# PriusPP-esp12e.net
KiCad netlist of a schematic drawn in EAGLE
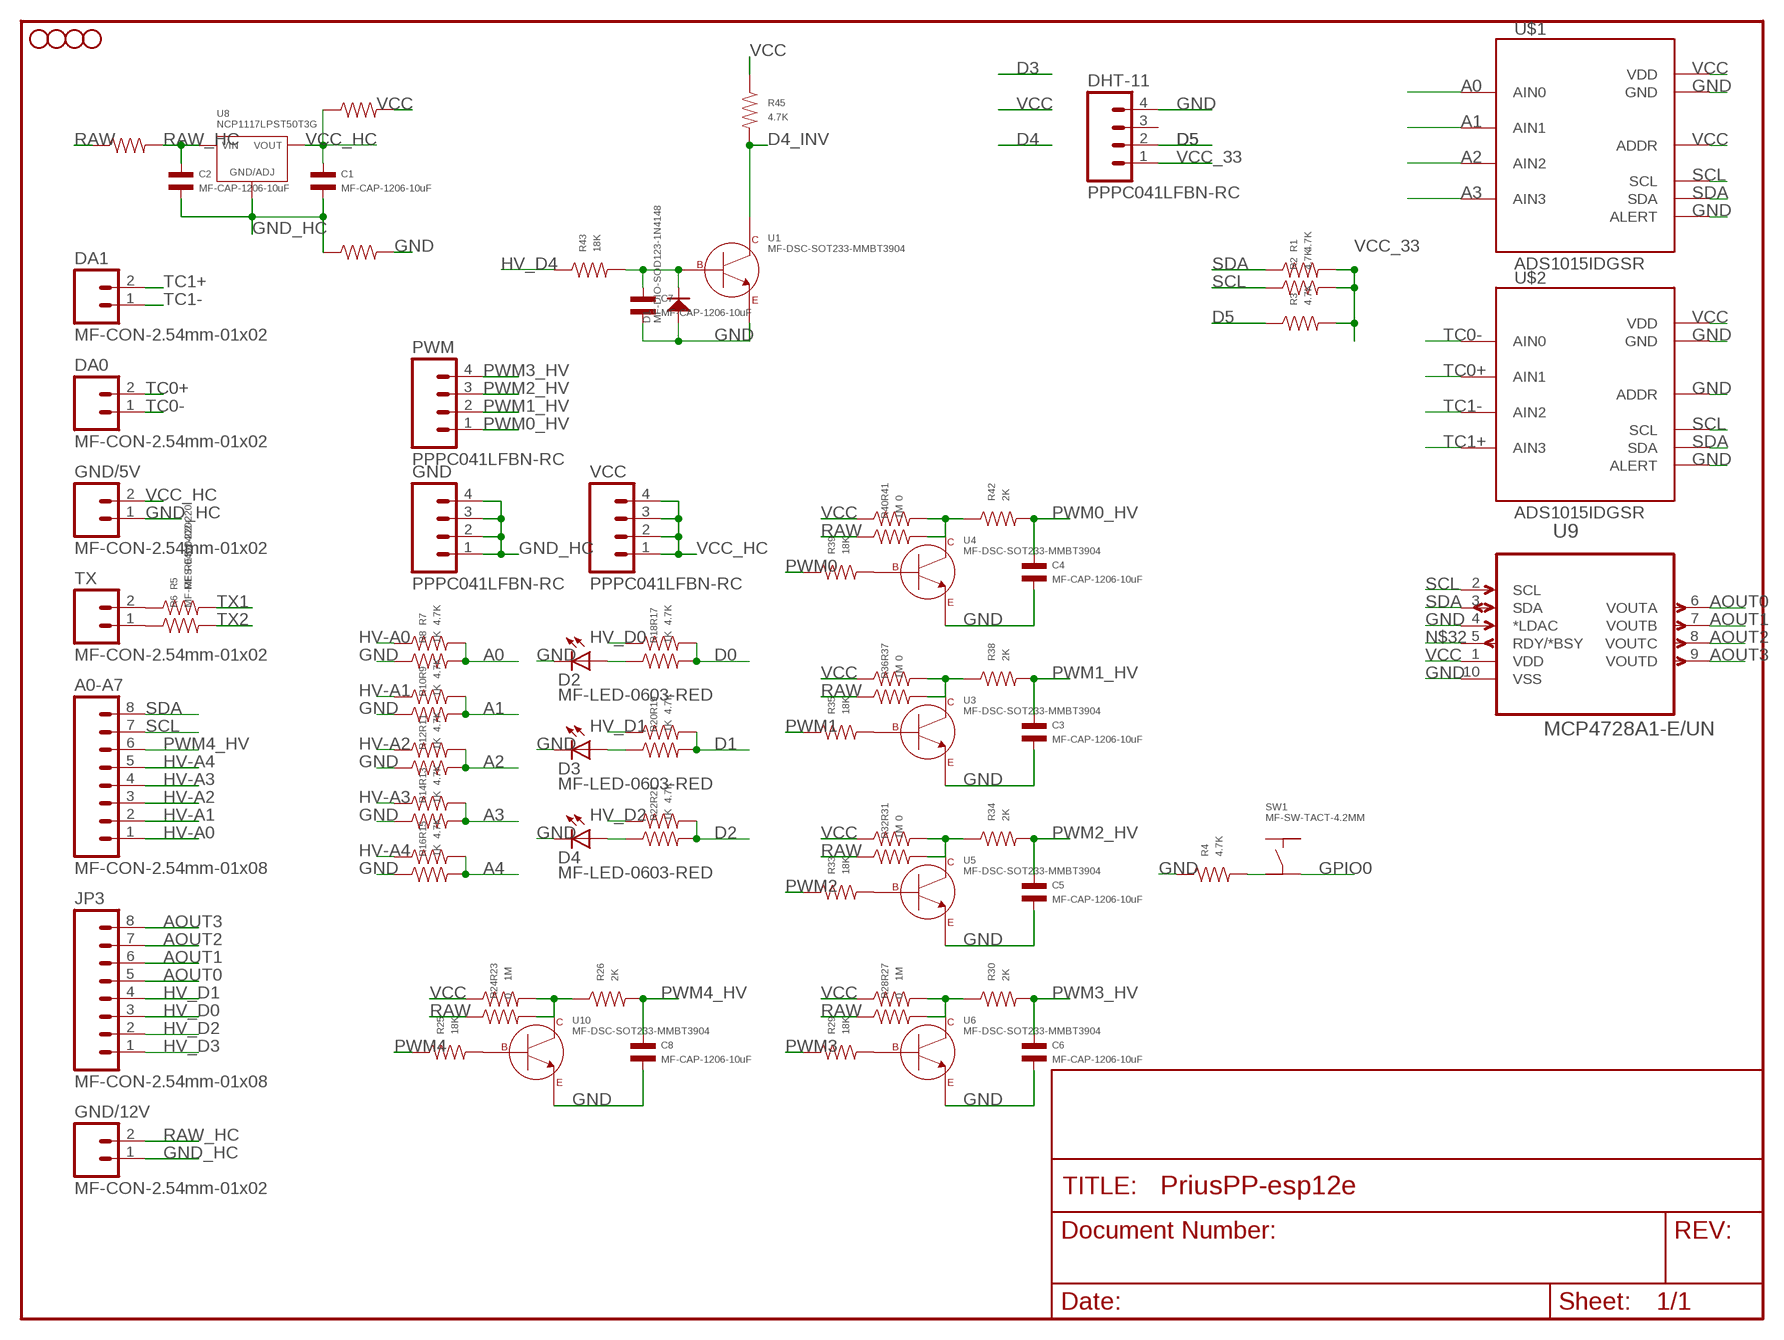
[diagram p0: schematic, sheet 1]

(export (version "E")
  (design (tool "Eeschema 10.0.6"))
  (components
    (comp (ref "A0-A7")
      (value "MF-CON-2.54mm-01x08")
      (footprint "eagle-import:1X08")
      (libsource (lib "eagle-import") (part "M081X08"))
    )
    (comp (ref "C1")
      (value "MF-CAP-1206-10uF")
      (footprint "eagle-import:C1206")
      (libsource (lib "eagle-import") (part "CAPACITOR_NP_1206"))
    )
    (comp (ref "C2")
      (value "MF-CAP-1206-10uF")
      (footprint "eagle-import:C1206")
      (libsource (lib "eagle-import") (part "CAPACITOR_NP_1206"))
    )
    (comp (ref "C3")
      (value "MF-CAP-1206-10uF")
      (footprint "eagle-import:C1206")
      (libsource (lib "eagle-import") (part "CAPACITOR_NP_1206"))
    )
    (comp (ref "C4")
      (value "MF-CAP-1206-10uF")
      (footprint "eagle-import:C1206")
      (libsource (lib "eagle-import") (part "CAPACITOR_NP_1206"))
    )
    (comp (ref "C5")
      (value "MF-CAP-1206-10uF")
      (footprint "eagle-import:C1206")
      (libsource (lib "eagle-import") (part "CAPACITOR_NP_1206"))
    )
    (comp (ref "C6")
      (value "MF-CAP-1206-10uF")
      (footprint "eagle-import:C1206")
      (libsource (lib "eagle-import") (part "CAPACITOR_NP_1206"))
    )
    (comp (ref "C7")
      (value "MF-CAP-1206-10uF")
      (footprint "eagle-import:C1206")
      (libsource (lib "eagle-import") (part "CAPACITOR_NP_1206"))
    )
    (comp (ref "C8")
      (value "MF-CAP-1206-10uF")
      (footprint "eagle-import:C1206")
      (libsource (lib "eagle-import") (part "CAPACITOR_NP_1206"))
    )
    (comp (ref "D1")
      (value "MF-DIO-SOD123-1N4148")
      (footprint "eagle-import:SOD-123")
      (fields (field (name "HOUSEPART") "YES"))
      (libsource (lib "eagle-import") (part "DIODES_SOD-123_1N4148"))
    )
    (comp (ref "D2")
      (value "MF-LED-0603-RED")
      (footprint "eagle-import:LED-0603")
      (libsource (lib "eagle-import") (part "LED-RED0603"))
    )
    (comp (ref "D3")
      (value "MF-LED-0603-RED")
      (footprint "eagle-import:LED-0603")
      (libsource (lib "eagle-import") (part "LED-RED0603"))
    )
    (comp (ref "D4")
      (value "MF-LED-0603-RED")
      (footprint "eagle-import:LED-0603")
      (libsource (lib "eagle-import") (part "LED-RED0603"))
    )
    (comp (ref "DA0")
      (value "MF-CON-2.54mm-01x02")
      (footprint "eagle-import:1X02")
      (libsource (lib "eagle-import") (part "M02PTH"))
    )
    (comp (ref "DA1")
      (value "MF-CON-2.54mm-01x02")
      (footprint "eagle-import:1X02")
      (libsource (lib "eagle-import") (part "M02PTH"))
    )
    (comp (ref "DHT-11")
      (value "PPPC041LFBN-RC")
      (footprint "eagle-import:1X04")
      (libsource (lib "eagle-import") (part "M04PTH"))
    )
    (comp (ref "GND")
      (value "PPPC041LFBN-RC")
      (footprint "eagle-import:1X04")
      (libsource (lib "eagle-import") (part "M04PTH"))
    )
    (comp (ref "GND/5V")
      (value "MF-CON-2.54mm-01x02")
      (footprint "eagle-import:1X02")
      (libsource (lib "eagle-import") (part "M02PTH"))
    )
    (comp (ref "GND/12V")
      (value "MF-CON-2.54mm-01x02")
      (footprint "eagle-import:1X02")
      (libsource (lib "eagle-import") (part "M02PTH"))
    )
    (comp (ref "JP3")
      (value "MF-CON-2.54mm-01x08")
      (footprint "eagle-import:1X08")
      (libsource (lib "eagle-import") (part "M081X08"))
    )
    (comp (ref "PWM")
      (value "PPPC041LFBN-RC")
      (footprint "eagle-import:1X04")
      (libsource (lib "eagle-import") (part "M04PTH"))
    )
    (comp (ref "R1")
      (value "4.7K")
      (footprint "eagle-import:R0402")
      (libsource (lib "eagle-import") (part "RESISTOR_0402"))
    )
    (comp (ref "R2")
      (value "4.7K")
      (footprint "eagle-import:R0402")
      (libsource (lib "eagle-import") (part "RESISTOR_0402"))
    )
    (comp (ref "R3")
      (value "4.7K")
      (footprint "eagle-import:R0402")
      (libsource (lib "eagle-import") (part "RESISTOR_0402"))
    )
    (comp (ref "R4")
      (value "4.7K")
      (footprint "eagle-import:R0402")
      (libsource (lib "eagle-import") (part "RESISTOR_0402"))
    )
    (comp (ref "R5")
      (value "MF-RES-0402-220")
      (footprint "eagle-import:R0402")
      (libsource (lib "eagle-import") (part "RESISTOR_0402"))
    )
    (comp (ref "R6")
      (value "MF-RES-0402-220")
      (footprint "eagle-import:R0402")
      (libsource (lib "eagle-import") (part "RESISTOR_0402"))
    )
    (comp (ref "R7")
      (value "4.7K")
      (footprint "eagle-import:R0402")
      (libsource (lib "eagle-import") (part "RESISTOR_0402"))
    )
    (comp (ref "R8")
      (value "1K")
      (footprint "eagle-import:R0402")
      (libsource (lib "eagle-import") (part "RESISTOR_0402"))
    )
    (comp (ref "R9")
      (value "4.7K")
      (footprint "eagle-import:R0402")
      (libsource (lib "eagle-import") (part "RESISTOR_0402"))
    )
    (comp (ref "R10")
      (value "1K")
      (footprint "eagle-import:R0402")
      (libsource (lib "eagle-import") (part "RESISTOR_0402"))
    )
    (comp (ref "R11")
      (value "4.7K")
      (footprint "eagle-import:R0402")
      (libsource (lib "eagle-import") (part "RESISTOR_0402"))
    )
    (comp (ref "R12")
      (value "1K")
      (footprint "eagle-import:R0402")
      (libsource (lib "eagle-import") (part "RESISTOR_0402"))
    )
    (comp (ref "R13")
      (value "4.7K")
      (footprint "eagle-import:R0402")
      (libsource (lib "eagle-import") (part "RESISTOR_0402"))
    )
    (comp (ref "R14")
      (value "1K")
      (footprint "eagle-import:R0402")
      (libsource (lib "eagle-import") (part "RESISTOR_0402"))
    )
    (comp (ref "R15")
      (value "4.7K")
      (footprint "eagle-import:R0402")
      (libsource (lib "eagle-import") (part "RESISTOR_0402"))
    )
    (comp (ref "R16")
      (value "1K")
      (footprint "eagle-import:R0402")
      (libsource (lib "eagle-import") (part "RESISTOR_0402"))
    )
    (comp (ref "R17")
      (value "4.7K")
      (footprint "eagle-import:R0402")
      (libsource (lib "eagle-import") (part "RESISTOR_0402"))
    )
    (comp (ref "R18")
      (value "1K")
      (footprint "eagle-import:R0402")
      (libsource (lib "eagle-import") (part "RESISTOR_0402"))
    )
    (comp (ref "R19")
      (value "4.7K")
      (footprint "eagle-import:R0402")
      (libsource (lib "eagle-import") (part "RESISTOR_0402"))
    )
    (comp (ref "R20")
      (value "1K")
      (footprint "eagle-import:R0402")
      (libsource (lib "eagle-import") (part "RESISTOR_0402"))
    )
    (comp (ref "R21")
      (value "4.7K")
      (footprint "eagle-import:R0402")
      (libsource (lib "eagle-import") (part "RESISTOR_0402"))
    )
    (comp (ref "R22")
      (value "1K")
      (footprint "eagle-import:R0402")
      (libsource (lib "eagle-import") (part "RESISTOR_0402"))
    )
    (comp (ref "R23")
      (value "1M")
      (footprint "eagle-import:R0402")
      (libsource (lib "eagle-import") (part "RESISTOR_0402"))
    )
    (comp (ref "R24")
      (value "0")
      (footprint "eagle-import:R0402")
      (libsource (lib "eagle-import") (part "RESISTOR_0402"))
    )
    (comp (ref "R25")
      (value "18K")
      (footprint "eagle-import:R0402")
      (libsource (lib "eagle-import") (part "RESISTOR_0402"))
    )
    (comp (ref "R26")
      (value "2K")
      (footprint "eagle-import:R0402")
      (libsource (lib "eagle-import") (part "RESISTOR_0402"))
    )
    (comp (ref "R27")
      (value "1M")
      (footprint "eagle-import:R0402")
      (libsource (lib "eagle-import") (part "RESISTOR_0402"))
    )
    (comp (ref "R28")
      (value "0")
      (footprint "eagle-import:R0402")
      (libsource (lib "eagle-import") (part "RESISTOR_0402"))
    )
    (comp (ref "R29")
      (value "18K")
      (footprint "eagle-import:R0402")
      (libsource (lib "eagle-import") (part "RESISTOR_0402"))
    )
    (comp (ref "R30")
      (value "2K")
      (footprint "eagle-import:R0402")
      (libsource (lib "eagle-import") (part "RESISTOR_0402"))
    )
    (comp (ref "R31")
      (value "0")
      (footprint "eagle-import:R0402")
      (libsource (lib "eagle-import") (part "RESISTOR_0402"))
    )
    (comp (ref "R32")
      (value "1M")
      (footprint "eagle-import:R0402")
      (libsource (lib "eagle-import") (part "RESISTOR_0402"))
    )
    (comp (ref "R33")
      (value "18K")
      (footprint "eagle-import:R0402")
      (libsource (lib "eagle-import") (part "RESISTOR_0402"))
    )
    (comp (ref "R34")
      (value "2K")
      (footprint "eagle-import:R0402")
      (libsource (lib "eagle-import") (part "RESISTOR_0402"))
    )
    (comp (ref "R35")
      (value "18K")
      (footprint "eagle-import:R0402")
      (libsource (lib "eagle-import") (part "RESISTOR_0402"))
    )
    (comp (ref "R36")
      (value "1M")
      (footprint "eagle-import:R0402")
      (libsource (lib "eagle-import") (part "RESISTOR_0402"))
    )
    (comp (ref "R37")
      (value "0")
      (footprint "eagle-import:R0402")
      (libsource (lib "eagle-import") (part "RESISTOR_0402"))
    )
    (comp (ref "R38")
      (value "2K")
      (footprint "eagle-import:R0402")
      (libsource (lib "eagle-import") (part "RESISTOR_0402"))
    )
    (comp (ref "R39")
      (value "18K")
      (footprint "eagle-import:R0402")
      (libsource (lib "eagle-import") (part "RESISTOR_0402"))
    )
    (comp (ref "R40")
      (value "1M")
      (footprint "eagle-import:R0402")
      (libsource (lib "eagle-import") (part "RESISTOR_0402"))
    )
    (comp (ref "R41")
      (value "0")
      (footprint "eagle-import:R0402")
      (libsource (lib "eagle-import") (part "RESISTOR_0402"))
    )
    (comp (ref "R42")
      (value "2K")
      (footprint "eagle-import:R0402")
      (libsource (lib "eagle-import") (part "RESISTOR_0402"))
    )
    (comp (ref "R43")
      (value "18K")
      (footprint "eagle-import:R0402")
      (libsource (lib "eagle-import") (part "RESISTOR_0402"))
    )
    (comp (ref "R45")
      (value "4.7K")
      (footprint "eagle-import:R0402")
      (libsource (lib "eagle-import") (part "RESISTOR_0402"))
    )
    (comp (ref "RIN7")
      (value "MF-RES-0603-0")
      (footprint "eagle-import:1206")
      (libsource (lib "eagle-import") (part "RESISTOR1206"))
    )
    (comp (ref "RIN8")
      (value "MF-RES-0603-0")
      (footprint "eagle-import:1206")
      (libsource (lib "eagle-import") (part "RESISTOR1206"))
    )
    (comp (ref "RIN19")
      (value "MF-RES-0603-0")
      (footprint "eagle-import:1206")
      (libsource (lib "eagle-import") (part "RESISTOR1206"))
    )
    (comp (ref "STANDOFF2")
      (value "STAND-OFF")
      (footprint "eagle-import:STAND-OFF")
      (libsource (lib "eagle-import") (part "STAND-OFF"))
    )
    (comp (ref "STANDOFF3")
      (value "STAND-OFF")
      (footprint "eagle-import:STAND-OFF")
      (libsource (lib "eagle-import") (part "STAND-OFF"))
    )
    (comp (ref "STANDOFF4")
      (value "STAND-OFF")
      (footprint "eagle-import:STAND-OFF")
      (libsource (lib "eagle-import") (part "STAND-OFF"))
    )
    (comp (ref "STANDOFF5")
      (value "STAND-OFF")
      (footprint "eagle-import:STAND-OFF")
      (libsource (lib "eagle-import") (part "STAND-OFF"))
    )
    (comp (ref "SW1")
      (value "MF-SW-TACT-4.2MM")
      (footprint "eagle-import:TACT4.2MM")
      (fields (field (name "HOUSEPART") "YES"))
      (libsource (lib "eagle-import") (part "TACT_4.2MM"))
    )
    (comp (ref "TX")
      (value "MF-CON-2.54mm-01x02")
      (footprint "eagle-import:1X02")
      (libsource (lib "eagle-import") (part "M02PTH"))
    )
    (comp (ref "U$1")
      (value "ADS1015IDGSR")
      (footprint "eagle-import:MSOP10_0.5")
      (libsource (lib "eagle-import") (part "ADS1015IDGT"))
    )
    (comp (ref "U$2")
      (value "ADS1015IDGSR")
      (footprint "eagle-import:MSOP10_0.5")
      (libsource (lib "eagle-import") (part "ADS1015IDGT"))
    )
    (comp (ref "U1")
      (value "MF-DSC-SOT233-MMBT3904")
      (footprint "eagle-import:SOT-23-3")
      (fields (field (name "HOUSEPART") "YES"))
      (libsource (lib "eagle-import") (part "NPN_BJT_SOT-23-3MMBT3904"))
    )
    (comp (ref "U3")
      (value "MF-DSC-SOT233-MMBT3904")
      (footprint "eagle-import:SOT-23-3")
      (fields (field (name "HOUSEPART") "YES"))
      (libsource (lib "eagle-import") (part "NPN_BJT_SOT-23-3MMBT3904"))
    )
    (comp (ref "U4")
      (value "MF-DSC-SOT233-MMBT3904")
      (footprint "eagle-import:SOT-23-3")
      (fields (field (name "HOUSEPART") "YES"))
      (libsource (lib "eagle-import") (part "NPN_BJT_SOT-23-3MMBT3904"))
    )
    (comp (ref "U5")
      (value "MF-DSC-SOT233-MMBT3904")
      (footprint "eagle-import:SOT-23-3")
      (fields (field (name "HOUSEPART") "YES"))
      (libsource (lib "eagle-import") (part "NPN_BJT_SOT-23-3MMBT3904"))
    )
    (comp (ref "U6")
      (value "MF-DSC-SOT233-MMBT3904")
      (footprint "eagle-import:SOT-23-3")
      (fields (field (name "HOUSEPART") "YES"))
      (libsource (lib "eagle-import") (part "NPN_BJT_SOT-23-3MMBT3904"))
    )
    (comp (ref "U8")
      (value "NCP1117LPST50T3G")
      (footprint "eagle-import:SOT-223-3")
      (fields (field (name "HOUSEPART") "NO"))
      (libsource (lib "eagle-import") (part "NCP1117LPST50T3G"))
    )
    (comp (ref "U9")
      (value "MCP4728A1-E/UN")
      (footprint "eagle-import:SOP50P490X110-10N")
      (fields (field (name "MPN") "MCP4728-E/UN"))
      (libsource (lib "eagle-import") (part "MCP4728-E/UN"))
    )
    (comp (ref "U10")
      (value "MF-DSC-SOT233-MMBT3904")
      (footprint "eagle-import:SOT-23-3")
      (fields (field (name "HOUSEPART") "YES"))
      (libsource (lib "eagle-import") (part "NPN_BJT_SOT-23-3MMBT3904"))
    )
    (comp (ref "VCC")
      (value "PPPC041LFBN-RC")
      (footprint "eagle-import:1X04")
      (libsource (lib "eagle-import") (part "M04PTH"))
    )
  )
  (nets
    (net (code "1") (name "/A0") (class "Default")
      (node (ref "R7") (pin "P$2") (pinfunction "P$2_P$2") (pintype "passive"))
      (node (ref "R8") (pin "P$2") (pinfunction "P$2_P$2") (pintype "passive"))
      (node (ref "U$1") (pin "4") (pinfunction "AIN0_4") (pintype "input"))
    )
    (net (code "2") (name "/A1") (class "Default")
      (node (ref "R10") (pin "P$2") (pinfunction "P$2_P$2") (pintype "passive"))
      (node (ref "R9") (pin "P$2") (pinfunction "P$2_P$2") (pintype "passive"))
      (node (ref "U$1") (pin "5") (pinfunction "AIN1_5") (pintype "input"))
    )
    (net (code "3") (name "/A2") (class "Default")
      (node (ref "R11") (pin "P$2") (pinfunction "P$2_P$2") (pintype "passive"))
      (node (ref "R12") (pin "P$2") (pinfunction "P$2_P$2") (pintype "passive"))
      (node (ref "U$1") (pin "6") (pinfunction "AIN2_6") (pintype "input"))
    )
    (net (code "4") (name "/A3") (class "Default")
      (node (ref "R13") (pin "P$2") (pinfunction "P$2_P$2") (pintype "passive"))
      (node (ref "R14") (pin "P$2") (pinfunction "P$2_P$2") (pintype "passive"))
      (node (ref "U$1") (pin "7") (pinfunction "AIN3_7") (pintype "input"))
    )
    (net (code "5") (name "/A4") (class "Default")
      (node (ref "R15") (pin "P$2") (pinfunction "P$2_P$2") (pintype "passive"))
      (node (ref "R16") (pin "P$2") (pinfunction "P$2_P$2") (pintype "passive"))
    )
    (net (code "6") (name "/AOUT0") (class "Default")
      (node (ref "JP3") (pin "5") (pinfunction "5_5") (pintype "passive"))
      (node (ref "U9") (pin "6") (pinfunction "VOUTA_6") (pintype "output"))
    )
    (net (code "7") (name "/AOUT1") (class "Default")
      (node (ref "JP3") (pin "6") (pinfunction "6_6") (pintype "passive"))
      (node (ref "U9") (pin "7") (pinfunction "VOUTB_7") (pintype "output"))
    )
    (net (code "8") (name "/AOUT2") (class "Default")
      (node (ref "JP3") (pin "7") (pinfunction "7_7") (pintype "passive"))
      (node (ref "U9") (pin "8") (pinfunction "VOUTC_8") (pintype "output"))
    )
    (net (code "9") (name "/AOUT3") (class "Default")
      (node (ref "JP3") (pin "8") (pinfunction "8_8") (pintype "passive"))
      (node (ref "U9") (pin "9") (pinfunction "VOUTD_9") (pintype "output"))
    )
    (net (code "10") (name "/D0") (class "Default")
      (node (ref "R17") (pin "P$2") (pinfunction "P$2_P$2") (pintype "passive"))
      (node (ref "R18") (pin "P$2") (pinfunction "P$2_P$2") (pintype "passive"))
    )
    (net (code "11") (name "/D1") (class "Default")
      (node (ref "R19") (pin "P$2") (pinfunction "P$2_P$2") (pintype "passive"))
      (node (ref "R20") (pin "P$2") (pinfunction "P$2_P$2") (pintype "passive"))
    )
    (net (code "12") (name "/D2") (class "Default")
      (node (ref "R21") (pin "P$2") (pinfunction "P$2_P$2") (pintype "passive"))
      (node (ref "R22") (pin "P$2") (pinfunction "P$2_P$2") (pintype "passive"))
    )
    (net (code "15") (name "/D4_INV") (class "Default")
      (node (ref "R45") (pin "P$2") (pinfunction "P$2_P$2") (pintype "passive"))
      (node (ref "U1") (pin "P$3") (pinfunction "COLLECTOR_P$3") (pintype "bidirectional"))
    )
    (net (code "16") (name "/D5") (class "Default")
      (node (ref "DHT-11") (pin "2") (pinfunction "2_2") (pintype "passive"))
      (node (ref "R3") (pin "P$1") (pinfunction "P$1_P$1") (pintype "passive"))
    )
    (net (code "17") (name "/GND") (class "Default")
      (node (ref "C3") (pin "P$2") (pinfunction "P$2_P$2") (pintype "passive"))
      (node (ref "C4") (pin "P$2") (pinfunction "P$2_P$2") (pintype "passive"))
      (node (ref "C5") (pin "P$2") (pinfunction "P$2_P$2") (pintype "passive"))
      (node (ref "C6") (pin "P$2") (pinfunction "P$2_P$2") (pintype "passive"))
      (node (ref "C7") (pin "P$2") (pinfunction "P$2_P$2") (pintype "passive"))
      (node (ref "C8") (pin "P$2") (pinfunction "P$2_P$2") (pintype "passive"))
      (node (ref "D1") (pin "ANODE") (pinfunction "ANODE_ANODE") (pintype "bidirectional"))
      (node (ref "D2") (pin "C") (pinfunction "C_C") (pintype "passive"))
      (node (ref "D3") (pin "C") (pinfunction "C_C") (pintype "passive"))
      (node (ref "D4") (pin "C") (pinfunction "C_C") (pintype "passive"))
      (node (ref "DHT-11") (pin "4") (pinfunction "4_4") (pintype "passive"))
      (node (ref "R10") (pin "P$1") (pinfunction "P$1_P$1") (pintype "passive"))
      (node (ref "R12") (pin "P$1") (pinfunction "P$1_P$1") (pintype "passive"))
      (node (ref "R14") (pin "P$1") (pinfunction "P$1_P$1") (pintype "passive"))
      (node (ref "R16") (pin "P$1") (pinfunction "P$1_P$1") (pintype "passive"))
      (node (ref "R4") (pin "P$1") (pinfunction "P$1_P$1") (pintype "passive"))
      (node (ref "R8") (pin "P$1") (pinfunction "P$1_P$1") (pintype "passive"))
      (node (ref "RIN8") (pin "2") (pinfunction "2_2") (pintype "passive"))
      (node (ref "U$1") (pin "2") (pinfunction "ALERT_2") (pintype "output"))
      (node (ref "U$1") (pin "3") (pinfunction "GND_3") (pintype "power_in"))
      (node (ref "U$2") (pin "1") (pinfunction "ADDR_1") (pintype "input"))
      (node (ref "U$2") (pin "2") (pinfunction "ALERT_2") (pintype "output"))
      (node (ref "U$2") (pin "3") (pinfunction "GND_3") (pintype "power_in"))
      (node (ref "U1") (pin "P$2") (pinfunction "EMITTER_P$2") (pintype "bidirectional"))
      (node (ref "U10") (pin "P$2") (pinfunction "EMITTER_P$2") (pintype "bidirectional"))
      (node (ref "U3") (pin "P$2") (pinfunction "EMITTER_P$2") (pintype "bidirectional"))
      (node (ref "U4") (pin "P$2") (pinfunction "EMITTER_P$2") (pintype "bidirectional"))
      (node (ref "U5") (pin "P$2") (pinfunction "EMITTER_P$2") (pintype "bidirectional"))
      (node (ref "U6") (pin "P$2") (pinfunction "EMITTER_P$2") (pintype "bidirectional"))
      (node (ref "U9") (pin "10") (pinfunction "VSS_10") (pintype "power_in"))
      (node (ref "U9") (pin "4") (pinfunction "*LDAC_4") (pintype "input"))
    )
    (net (code "18") (name "/GND_HC") (class "Default")
      (node (ref "C1") (pin "P$2") (pinfunction "P$2_P$2") (pintype "passive"))
      (node (ref "C2") (pin "P$2") (pinfunction "P$2_P$2") (pintype "passive"))
      (node (ref "GND") (pin "1") (pinfunction "1_1") (pintype "passive"))
      (node (ref "GND") (pin "2") (pinfunction "2_2") (pintype "passive"))
      (node (ref "GND") (pin "3") (pinfunction "3_3") (pintype "passive"))
      (node (ref "GND") (pin "4") (pinfunction "4_4") (pintype "passive"))
      (node (ref "GND/12V") (pin "1") (pinfunction "1_1") (pintype "passive"))
      (node (ref "GND/5V") (pin "1") (pinfunction "1_1") (pintype "passive"))
      (node (ref "RIN8") (pin "1") (pinfunction "1_1") (pintype "passive"))
      (node (ref "U8") (pin "P$2") (pinfunction "GND/ADJ_P$2") (pintype "bidirectional"))
    )
    (net (code "19") (name "/GPIO0") (class "Default")
      (node (ref "SW1") (pin "P$4") (pinfunction "P$4_P$4") (pintype "bidirectional"))
    )
    (net (code "20") (name "/HV-A0") (class "Default")
      (node (ref "A0-A7") (pin "1") (pinfunction "1_1") (pintype "passive"))
      (node (ref "R7") (pin "P$1") (pinfunction "P$1_P$1") (pintype "passive"))
    )
    (net (code "21") (name "/HV-A1") (class "Default")
      (node (ref "A0-A7") (pin "2") (pinfunction "2_2") (pintype "passive"))
      (node (ref "R9") (pin "P$1") (pinfunction "P$1_P$1") (pintype "passive"))
    )
    (net (code "22") (name "/HV-A2") (class "Default")
      (node (ref "A0-A7") (pin "3") (pinfunction "3_3") (pintype "passive"))
      (node (ref "R11") (pin "P$1") (pinfunction "P$1_P$1") (pintype "passive"))
    )
    (net (code "23") (name "/HV-A3") (class "Default")
      (node (ref "A0-A7") (pin "4") (pinfunction "4_4") (pintype "passive"))
      (node (ref "R13") (pin "P$1") (pinfunction "P$1_P$1") (pintype "passive"))
    )
    (net (code "24") (name "/HV-A4") (class "Default")
      (node (ref "A0-A7") (pin "5") (pinfunction "5_5") (pintype "passive"))
      (node (ref "R15") (pin "P$1") (pinfunction "P$1_P$1") (pintype "passive"))
    )
    (net (code "25") (name "/HV_D0") (class "Default")
      (node (ref "JP3") (pin "3") (pinfunction "3_3") (pintype "passive"))
      (node (ref "R17") (pin "P$1") (pinfunction "P$1_P$1") (pintype "passive"))
    )
    (net (code "26") (name "/HV_D1") (class "Default")
      (node (ref "JP3") (pin "4") (pinfunction "4_4") (pintype "passive"))
      (node (ref "R19") (pin "P$1") (pinfunction "P$1_P$1") (pintype "passive"))
    )
    (net (code "27") (name "/HV_D2") (class "Default")
      (node (ref "JP3") (pin "2") (pinfunction "2_2") (pintype "passive"))
      (node (ref "R21") (pin "P$1") (pinfunction "P$1_P$1") (pintype "passive"))
    )
    (net (code "28") (name "/HV_D3") (class "Default")
      (node (ref "JP3") (pin "1") (pinfunction "1_1") (pintype "passive"))
    )
    (net (code "29") (name "/HV_D4") (class "Default")
      (node (ref "R43") (pin "P$1") (pinfunction "P$1_P$1") (pintype "passive"))
    )
    (net (code "30") (name "/N$32") (class "Default")
      (node (ref "U9") (pin "5") (pinfunction "RDY/*BSY_5") (pintype "output"))
    )
    (net (code "31") (name "/PWM0") (class "Default")
      (node (ref "R39") (pin "P$1") (pinfunction "P$1_P$1") (pintype "passive"))
    )
    (net (code "32") (name "/PWM0_HV") (class "Default")
      (node (ref "C4") (pin "P$1") (pinfunction "P$1_P$1") (pintype "passive"))
      (node (ref "PWM") (pin "1") (pinfunction "1_1") (pintype "passive"))
      (node (ref "R42") (pin "P$2") (pinfunction "P$2_P$2") (pintype "passive"))
    )
    (net (code "33") (name "/PWM1") (class "Default")
      (node (ref "R35") (pin "P$1") (pinfunction "P$1_P$1") (pintype "passive"))
    )
    (net (code "34") (name "/PWM1_HV") (class "Default")
      (node (ref "C3") (pin "P$1") (pinfunction "P$1_P$1") (pintype "passive"))
      (node (ref "PWM") (pin "2") (pinfunction "2_2") (pintype "passive"))
      (node (ref "R38") (pin "P$2") (pinfunction "P$2_P$2") (pintype "passive"))
    )
    (net (code "35") (name "/PWM2") (class "Default")
      (node (ref "R33") (pin "P$1") (pinfunction "P$1_P$1") (pintype "passive"))
    )
    (net (code "36") (name "/PWM2_HV") (class "Default")
      (node (ref "C5") (pin "P$1") (pinfunction "P$1_P$1") (pintype "passive"))
      (node (ref "PWM") (pin "3") (pinfunction "3_3") (pintype "passive"))
      (node (ref "R34") (pin "P$2") (pinfunction "P$2_P$2") (pintype "passive"))
    )
    (net (code "37") (name "/PWM3") (class "Default")
      (node (ref "R29") (pin "P$1") (pinfunction "P$1_P$1") (pintype "passive"))
    )
    (net (code "38") (name "/PWM3_HV") (class "Default")
      (node (ref "C6") (pin "P$1") (pinfunction "P$1_P$1") (pintype "passive"))
      (node (ref "PWM") (pin "4") (pinfunction "4_4") (pintype "passive"))
      (node (ref "R30") (pin "P$2") (pinfunction "P$2_P$2") (pintype "passive"))
    )
    (net (code "39") (name "/PWM4") (class "Default")
      (node (ref "R25") (pin "P$1") (pinfunction "P$1_P$1") (pintype "passive"))
    )
    (net (code "40") (name "/PWM4_HV") (class "Default")
      (node (ref "A0-A7") (pin "6") (pinfunction "6_6") (pintype "passive"))
      (node (ref "C8") (pin "P$1") (pinfunction "P$1_P$1") (pintype "passive"))
      (node (ref "R26") (pin "P$2") (pinfunction "P$2_P$2") (pintype "passive"))
    )
    (net (code "41") (name "/RAW") (class "Default")
      (node (ref "R24") (pin "P$1") (pinfunction "P$1_P$1") (pintype "passive"))
      (node (ref "R28") (pin "P$1") (pinfunction "P$1_P$1") (pintype "passive"))
      (node (ref "R32") (pin "P$1") (pinfunction "P$1_P$1") (pintype "passive"))
      (node (ref "R36") (pin "P$1") (pinfunction "P$1_P$1") (pintype "passive"))
      (node (ref "R40") (pin "P$1") (pinfunction "P$1_P$1") (pintype "passive"))
      (node (ref "RIN19") (pin "1") (pinfunction "1_1") (pintype "passive"))
    )
    (net (code "42") (name "/RAW_HC") (class "Default")
      (node (ref "C2") (pin "P$1") (pinfunction "P$1_P$1") (pintype "passive"))
      (node (ref "GND/12V") (pin "2") (pinfunction "2_2") (pintype "passive"))
      (node (ref "RIN19") (pin "2") (pinfunction "2_2") (pintype "passive"))
      (node (ref "U8") (pin "P$4") (pinfunction "VIN_P$4") (pintype "bidirectional"))
    )
    (net (code "43") (name "/SCL") (class "Default")
      (node (ref "A0-A7") (pin "7") (pinfunction "7_7") (pintype "passive"))
      (node (ref "R2") (pin "P$1") (pinfunction "P$1_P$1") (pintype "passive"))
      (node (ref "U$1") (pin "10") (pinfunction "SCL_10") (pintype "bidirectional"))
      (node (ref "U$2") (pin "10") (pinfunction "SCL_10") (pintype "bidirectional"))
      (node (ref "U9") (pin "2") (pinfunction "SCL_2") (pintype "input"))
    )
    (net (code "44") (name "/SDA") (class "Default")
      (node (ref "A0-A7") (pin "8") (pinfunction "8_8") (pintype "passive"))
      (node (ref "R1") (pin "P$1") (pinfunction "P$1_P$1") (pintype "passive"))
      (node (ref "U$1") (pin "9") (pinfunction "SDA_9") (pintype "bidirectional"))
      (node (ref "U$2") (pin "9") (pinfunction "SDA_9") (pintype "bidirectional"))
      (node (ref "U9") (pin "3") (pinfunction "SDA_3") (pintype "bidirectional"))
    )
    (net (code "45") (name "/TC0+") (class "Default")
      (node (ref "DA0") (pin "2") (pinfunction "2_2") (pintype "passive"))
      (node (ref "U$2") (pin "5") (pinfunction "AIN1_5") (pintype "input"))
    )
    (net (code "46") (name "/TC0-") (class "Default")
      (node (ref "DA0") (pin "1") (pinfunction "1_1") (pintype "passive"))
      (node (ref "U$2") (pin "4") (pinfunction "AIN0_4") (pintype "input"))
    )
    (net (code "47") (name "/TC1+") (class "Default")
      (node (ref "DA1") (pin "2") (pinfunction "2_2") (pintype "passive"))
      (node (ref "U$2") (pin "7") (pinfunction "AIN3_7") (pintype "input"))
    )
    (net (code "48") (name "/TC1-") (class "Default")
      (node (ref "DA1") (pin "1") (pinfunction "1_1") (pintype "passive"))
      (node (ref "U$2") (pin "6") (pinfunction "AIN2_6") (pintype "input"))
    )
    (net (code "49") (name "/TX1") (class "Default")
      (node (ref "R5") (pin "P$2") (pinfunction "P$2_P$2") (pintype "passive"))
    )
    (net (code "50") (name "/TX2") (class "Default")
      (node (ref "R6") (pin "P$2") (pinfunction "P$2_P$2") (pintype "passive"))
    )
    (net (code "51") (name "/VCC") (class "Default")
      (node (ref "R23") (pin "P$1") (pinfunction "P$1_P$1") (pintype "passive"))
      (node (ref "R27") (pin "P$1") (pinfunction "P$1_P$1") (pintype "passive"))
      (node (ref "R31") (pin "P$1") (pinfunction "P$1_P$1") (pintype "passive"))
      (node (ref "R37") (pin "P$1") (pinfunction "P$1_P$1") (pintype "passive"))
      (node (ref "R41") (pin "P$1") (pinfunction "P$1_P$1") (pintype "passive"))
      (node (ref "R45") (pin "P$1") (pinfunction "P$1_P$1") (pintype "passive"))
      (node (ref "RIN7") (pin "2") (pinfunction "2_2") (pintype "passive"))
      (node (ref "U$1") (pin "1") (pinfunction "ADDR_1") (pintype "input"))
      (node (ref "U$1") (pin "8") (pinfunction "VDD_8") (pintype "power_in"))
      (node (ref "U$2") (pin "8") (pinfunction "VDD_8") (pintype "power_in"))
      (node (ref "U9") (pin "1") (pinfunction "VDD_1") (pintype "power_in"))
    )
    (net (code "52") (name "/VCC_33") (class "Default")
      (node (ref "DHT-11") (pin "1") (pinfunction "1_1") (pintype "passive"))
      (node (ref "R1") (pin "P$2") (pinfunction "P$2_P$2") (pintype "passive"))
      (node (ref "R2") (pin "P$2") (pinfunction "P$2_P$2") (pintype "passive"))
      (node (ref "R3") (pin "P$2") (pinfunction "P$2_P$2") (pintype "passive"))
    )
    (net (code "53") (name "/VCC_HC") (class "Default")
      (node (ref "C1") (pin "P$1") (pinfunction "P$1_P$1") (pintype "passive"))
      (node (ref "GND/5V") (pin "2") (pinfunction "2_2") (pintype "passive"))
      (node (ref "RIN7") (pin "1") (pinfunction "1_1") (pintype "passive"))
      (node (ref "U8") (pin "P$1") (pinfunction "VOUT_P$1") (pintype "bidirectional"))
      (node (ref "U8") (pin "P$3") (pinfunction "VOUT_P$3") (pintype "bidirectional"))
      (node (ref "VCC") (pin "1") (pinfunction "1_1") (pintype "passive"))
      (node (ref "VCC") (pin "2") (pinfunction "2_2") (pintype "passive"))
      (node (ref "VCC") (pin "3") (pinfunction "3_3") (pintype "passive"))
      (node (ref "VCC") (pin "4") (pinfunction "4_4") (pintype "passive"))
    )
    (net (code "54") (name "Net-(D2-PadA)") (class "Default")
      (node (ref "D2") (pin "A") (pinfunction "A_A") (pintype "passive"))
      (node (ref "R18") (pin "P$1") (pinfunction "P$1_P$1") (pintype "passive"))
    )
    (net (code "55") (name "Net-(D3-PadA)") (class "Default")
      (node (ref "D3") (pin "A") (pinfunction "A_A") (pintype "passive"))
      (node (ref "R20") (pin "P$1") (pinfunction "P$1_P$1") (pintype "passive"))
    )
    (net (code "56") (name "Net-(D4-PadA)") (class "Default")
      (node (ref "D4") (pin "A") (pinfunction "A_A") (pintype "passive"))
      (node (ref "R22") (pin "P$1") (pinfunction "P$1_P$1") (pintype "passive"))
    )
    (net (code "57") (name "Net-(R4-PadP$2)") (class "Default")
      (node (ref "R4") (pin "P$2") (pinfunction "P$2_P$2") (pintype "passive"))
      (node (ref "SW1") (pin "P$3") (pinfunction "P$3_P$3") (pintype "bidirectional"))
    )
    (net (code "58") (name "Net-(R5-PadP$1)") (class "Default")
      (node (ref "R5") (pin "P$1") (pinfunction "P$1_P$1") (pintype "passive"))
      (node (ref "TX") (pin "2") (pinfunction "2_2") (pintype "passive"))
    )
    (net (code "59") (name "Net-(R6-PadP$1)") (class "Default")
      (node (ref "R6") (pin "P$1") (pinfunction "P$1_P$1") (pintype "passive"))
      (node (ref "TX") (pin "1") (pinfunction "1_1") (pintype "passive"))
    )
    (net (code "60") (name "Net-(U1-BASE)") (class "Default")
      (node (ref "C7") (pin "P$1") (pinfunction "P$1_P$1") (pintype "passive"))
      (node (ref "D1") (pin "CATHODE") (pinfunction "CATHODE_CATHODE") (pintype "bidirectional"))
      (node (ref "R43") (pin "P$2") (pinfunction "P$2_P$2") (pintype "passive"))
      (node (ref "U1") (pin "P$1") (pinfunction "BASE_P$1") (pintype "bidirectional"))
    )
    (net (code "61") (name "Net-(U3-BASE)") (class "Default")
      (node (ref "R35") (pin "P$2") (pinfunction "P$2_P$2") (pintype "passive"))
      (node (ref "U3") (pin "P$1") (pinfunction "BASE_P$1") (pintype "bidirectional"))
    )
    (net (code "62") (name "Net-(U3-COLLECTOR)") (class "Default")
      (node (ref "R36") (pin "P$2") (pinfunction "P$2_P$2") (pintype "passive"))
      (node (ref "R37") (pin "P$2") (pinfunction "P$2_P$2") (pintype "passive"))
      (node (ref "R38") (pin "P$1") (pinfunction "P$1_P$1") (pintype "passive"))
      (node (ref "U3") (pin "P$3") (pinfunction "COLLECTOR_P$3") (pintype "bidirectional"))
    )
    (net (code "63") (name "Net-(U4-BASE)") (class "Default")
      (node (ref "R39") (pin "P$2") (pinfunction "P$2_P$2") (pintype "passive"))
      (node (ref "U4") (pin "P$1") (pinfunction "BASE_P$1") (pintype "bidirectional"))
    )
    (net (code "64") (name "Net-(U4-COLLECTOR)") (class "Default")
      (node (ref "R40") (pin "P$2") (pinfunction "P$2_P$2") (pintype "passive"))
      (node (ref "R41") (pin "P$2") (pinfunction "P$2_P$2") (pintype "passive"))
      (node (ref "R42") (pin "P$1") (pinfunction "P$1_P$1") (pintype "passive"))
      (node (ref "U4") (pin "P$3") (pinfunction "COLLECTOR_P$3") (pintype "bidirectional"))
    )
    (net (code "65") (name "Net-(U5-BASE)") (class "Default")
      (node (ref "R33") (pin "P$2") (pinfunction "P$2_P$2") (pintype "passive"))
      (node (ref "U5") (pin "P$1") (pinfunction "BASE_P$1") (pintype "bidirectional"))
    )
    (net (code "66") (name "Net-(U5-COLLECTOR)") (class "Default")
      (node (ref "R31") (pin "P$2") (pinfunction "P$2_P$2") (pintype "passive"))
      (node (ref "R32") (pin "P$2") (pinfunction "P$2_P$2") (pintype "passive"))
      (node (ref "R34") (pin "P$1") (pinfunction "P$1_P$1") (pintype "passive"))
      (node (ref "U5") (pin "P$3") (pinfunction "COLLECTOR_P$3") (pintype "bidirectional"))
    )
    (net (code "67") (name "Net-(U6-BASE)") (class "Default")
      (node (ref "R29") (pin "P$2") (pinfunction "P$2_P$2") (pintype "passive"))
      (node (ref "U6") (pin "P$1") (pinfunction "BASE_P$1") (pintype "bidirectional"))
    )
    (net (code "68") (name "Net-(U6-COLLECTOR)") (class "Default")
      (node (ref "R27") (pin "P$2") (pinfunction "P$2_P$2") (pintype "passive"))
      (node (ref "R28") (pin "P$2") (pinfunction "P$2_P$2") (pintype "passive"))
      (node (ref "R30") (pin "P$1") (pinfunction "P$1_P$1") (pintype "passive"))
      (node (ref "U6") (pin "P$3") (pinfunction "COLLECTOR_P$3") (pintype "bidirectional"))
    )
    (net (code "69") (name "Net-(U10-BASE)") (class "Default")
      (node (ref "R25") (pin "P$2") (pinfunction "P$2_P$2") (pintype "passive"))
      (node (ref "U10") (pin "P$1") (pinfunction "BASE_P$1") (pintype "bidirectional"))
    )
    (net (code "70") (name "Net-(U10-COLLECTOR)") (class "Default")
      (node (ref "R23") (pin "P$2") (pinfunction "P$2_P$2") (pintype "passive"))
      (node (ref "R24") (pin "P$2") (pinfunction "P$2_P$2") (pintype "passive"))
      (node (ref "R26") (pin "P$1") (pinfunction "P$1_P$1") (pintype "passive"))
      (node (ref "U10") (pin "P$3") (pinfunction "COLLECTOR_P$3") (pintype "bidirectional"))
    )
    (net (code "71") (name "unconnected-(DHT-11-Pad3)") (class "Default")
      (node (ref "DHT-11") (pin "3") (pinfunction "3_3") (pintype "passive"))
    )
    (net (code "72") (name "unconnected-(SW1-PadP$1)") (class "Default")
      (node (ref "SW1") (pin "P$1") (pinfunction "P$1_P$1") (pintype "bidirectional"))
    )
    (net (code "73") (name "unconnected-(SW1-PadP$2)") (class "Default")
      (node (ref "SW1") (pin "P$2") (pinfunction "P$2_P$2") (pintype "bidirectional"))
    )
  )
)
